# LED42056-Board.net
KiCad netlist of a schematic drawn in EAGLE
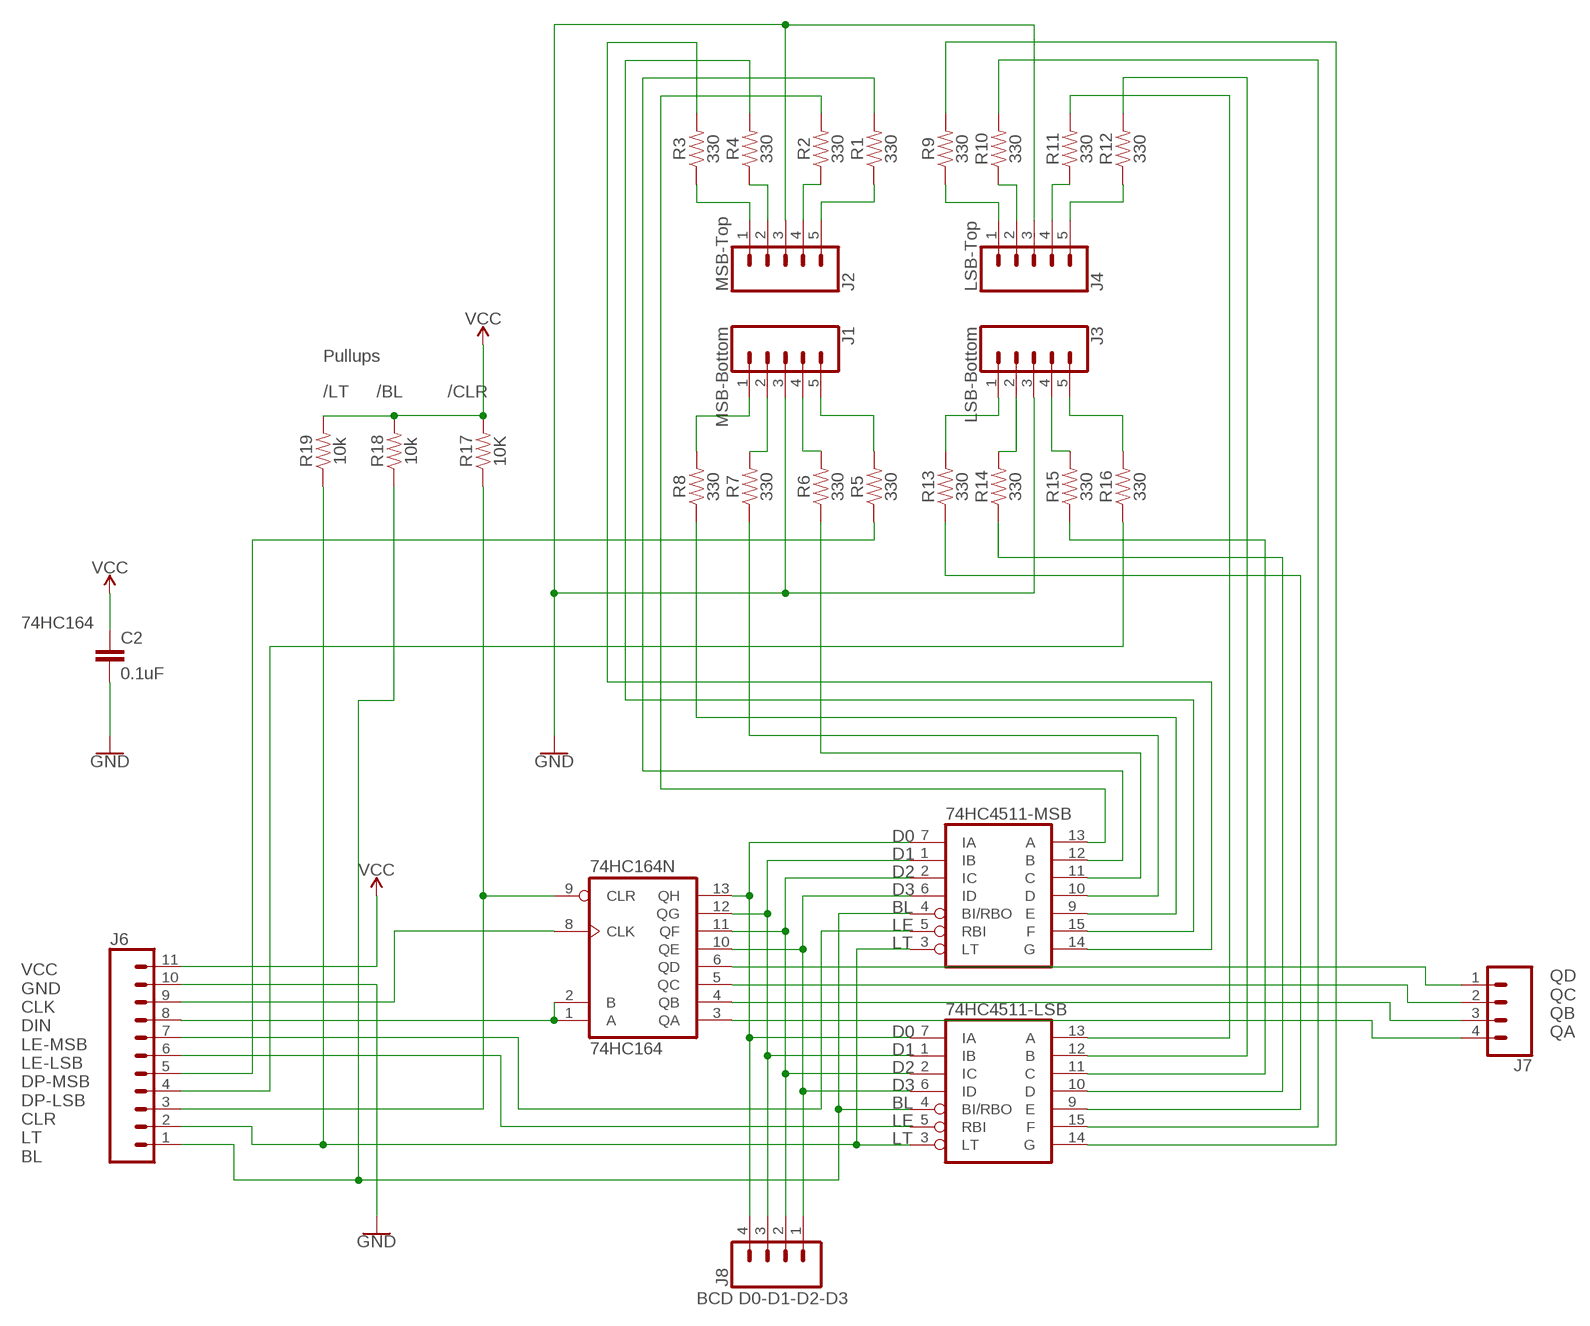
[diagram p0: schematic, sheet 1]

(export (version "E")
  (design (tool "Eeschema 10.0.6"))
  (components
    (comp (ref "74HC164")
      (value "74HC164N")
      (footprint "eagle-import:DIL14")
      (libsource (lib "eagle-import") (part "74164NHC"))
    )
    (comp (ref "74HC4511-LSB")
      (value "74LS47N")
      (footprint "eagle-import:DIL16")
      (libsource (lib "eagle-import") (part "7447NLS"))
    )
    (comp (ref "74HC4511-MSB")
      (value "74LS47N")
      (footprint "eagle-import:DIL16")
      (libsource (lib "eagle-import") (part "7447NLS"))
    )
    (comp (ref "C2")
      (value "0.1uF")
      (footprint "eagle-import:CAP-PTH-2.54")
      (libsource (lib "eagle-import") (part "22PF-PTH-2.54MM-200V-5%"))
    )
    (comp (ref "J1")
      (value "MSB-Bottom")
      (footprint "eagle-import:1X05_LOCK")
      (libsource (lib "eagle-import") (part "CONN_05LOCK"))
    )
    (comp (ref "J2")
      (value "MSB-Top")
      (footprint "eagle-import:1X05_LOCK")
      (libsource (lib "eagle-import") (part "CONN_05LOCK"))
    )
    (comp (ref "J3")
      (value "LSB-Bottom")
      (footprint "eagle-import:1X05_LOCK")
      (libsource (lib "eagle-import") (part "CONN_05LOCK"))
    )
    (comp (ref "J4")
      (value "LSB-Top")
      (footprint "eagle-import:1X05_LOCK")
      (libsource (lib "eagle-import") (part "CONN_05LOCK"))
    )
    (comp (ref "J6")
      (value "CONN_11LOCK")
      (footprint "eagle-import:1X11_LOCK")
      (libsource (lib "eagle-import") (part "CONN_11LOCK"))
    )
    (comp (ref "J7")
      (value "CONN_04LOCK")
      (footprint "eagle-import:1X04_LOCK")
      (libsource (lib "eagle-import") (part "CONN_04LOCK"))
    )
    (comp (ref "J8")
      (value "CONN_04LOCK")
      (footprint "eagle-import:1X04_LOCK")
      (libsource (lib "eagle-import") (part "CONN_04LOCK"))
    )
    (comp (ref "R1")
      (value "330")
      (footprint "eagle-import:AXIAL-0.3")
      (libsource (lib "eagle-import") (part "330OHM-HORIZ-1/10W-5%"))
    )
    (comp (ref "R2")
      (value "330")
      (footprint "eagle-import:AXIAL-0.3")
      (libsource (lib "eagle-import") (part "330OHM-HORIZ-1/10W-5%"))
    )
    (comp (ref "R3")
      (value "330")
      (footprint "eagle-import:AXIAL-0.3")
      (libsource (lib "eagle-import") (part "330OHM-HORIZ-1/10W-5%"))
    )
    (comp (ref "R4")
      (value "330")
      (footprint "eagle-import:AXIAL-0.3")
      (libsource (lib "eagle-import") (part "330OHM-HORIZ-1/10W-5%"))
    )
    (comp (ref "R5")
      (value "330")
      (footprint "eagle-import:AXIAL-0.3")
      (libsource (lib "eagle-import") (part "330OHM-HORIZ-1/10W-5%"))
    )
    (comp (ref "R6")
      (value "330")
      (footprint "eagle-import:AXIAL-0.3")
      (libsource (lib "eagle-import") (part "330OHM-HORIZ-1/10W-5%"))
    )
    (comp (ref "R7")
      (value "330")
      (footprint "eagle-import:AXIAL-0.3")
      (libsource (lib "eagle-import") (part "330OHM-HORIZ-1/10W-5%"))
    )
    (comp (ref "R8")
      (value "330")
      (footprint "eagle-import:AXIAL-0.3")
      (libsource (lib "eagle-import") (part "330OHM-HORIZ-1/10W-5%"))
    )
    (comp (ref "R9")
      (value "330")
      (footprint "eagle-import:AXIAL-0.3")
      (libsource (lib "eagle-import") (part "330OHM-HORIZ-1/10W-5%"))
    )
    (comp (ref "R10")
      (value "330")
      (footprint "eagle-import:AXIAL-0.3")
      (libsource (lib "eagle-import") (part "330OHM-HORIZ-1/10W-5%"))
    )
    (comp (ref "R11")
      (value "330")
      (footprint "eagle-import:AXIAL-0.3")
      (libsource (lib "eagle-import") (part "330OHM-HORIZ-1/10W-5%"))
    )
    (comp (ref "R12")
      (value "330")
      (footprint "eagle-import:AXIAL-0.3")
      (libsource (lib "eagle-import") (part "330OHM-HORIZ-1/10W-5%"))
    )
    (comp (ref "R13")
      (value "330")
      (footprint "eagle-import:AXIAL-0.3")
      (libsource (lib "eagle-import") (part "330OHM-HORIZ-1/10W-5%"))
    )
    (comp (ref "R14")
      (value "330")
      (footprint "eagle-import:AXIAL-0.3")
      (libsource (lib "eagle-import") (part "330OHM-HORIZ-1/10W-5%"))
    )
    (comp (ref "R15")
      (value "330")
      (footprint "eagle-import:AXIAL-0.3")
      (libsource (lib "eagle-import") (part "330OHM-HORIZ-1/10W-5%"))
    )
    (comp (ref "R16")
      (value "330")
      (footprint "eagle-import:AXIAL-0.3")
      (libsource (lib "eagle-import") (part "330OHM-HORIZ-1/10W-5%"))
    )
    (comp (ref "R17")
      (value "10K")
      (footprint "eagle-import:AXIAL-0.3")
      (libsource (lib "eagle-import") (part "330OHM-HORIZ-1/10W-5%"))
    )
    (comp (ref "R18")
      (value "10k")
      (footprint "eagle-import:AXIAL-0.3")
      (libsource (lib "eagle-import") (part "10KOHM-HORIZ-1/4W-1%"))
    )
    (comp (ref "R19")
      (value "10k")
      (footprint "eagle-import:AXIAL-0.3")
      (libsource (lib "eagle-import") (part "10KOHM-HORIZ-1/4W-1%"))
    )
  )
  (nets
    (net (code "1") (name "GND") (class "Default")
      (node (ref "C2") (pin "2") (pinfunction "2_2") (pintype "passive"))
      (node (ref "J1") (pin "3") (pinfunction "3_3") (pintype "passive"))
      (node (ref "J2") (pin "3") (pinfunction "3_3") (pintype "passive"))
      (node (ref "J3") (pin "3") (pinfunction "3_3") (pintype "passive"))
      (node (ref "J4") (pin "3") (pinfunction "3_3") (pintype "passive"))
      (node (ref "J6") (pin "10") (pinfunction "10_10") (pintype "passive"))
    )
    (net (code "2") (name "Net-(74HC164A-A)") (class "Default")
      (node (ref "74HC164") (pin "1") (pinfunction "A_1") (pintype "input"))
      (node (ref "74HC164") (pin "2") (pinfunction "B_2") (pintype "input"))
      (node (ref "J6") (pin "8") (pinfunction "8_8") (pintype "passive"))
    )
    (net (code "3") (name "Net-(74HC164A-CLK)") (class "Default")
      (node (ref "74HC164") (pin "8") (pinfunction "CLK_8") (pintype "input"))
      (node (ref "J6") (pin "9") (pinfunction "9_9") (pintype "passive"))
    )
    (net (code "4") (name "Net-(74HC164A-CLR)") (class "Default")
      (node (ref "74HC164") (pin "9") (pinfunction "CLR_9") (pintype "input"))
      (node (ref "J6") (pin "3") (pinfunction "3_3") (pintype "passive"))
      (node (ref "R17") (pin "P$1") (pinfunction "1_P$1") (pintype "passive"))
    )
    (net (code "5") (name "Net-(74HC164A-QA)") (class "Default")
      (node (ref "74HC164") (pin "3") (pinfunction "QA_3") (pintype "output"))
      (node (ref "J7") (pin "4") (pinfunction "4_4") (pintype "passive"))
    )
    (net (code "6") (name "Net-(74HC164A-QB)") (class "Default")
      (node (ref "74HC164") (pin "4") (pinfunction "QB_4") (pintype "output"))
      (node (ref "J7") (pin "3") (pinfunction "3_3") (pintype "passive"))
    )
    (net (code "7") (name "Net-(74HC164A-QC)") (class "Default")
      (node (ref "74HC164") (pin "5") (pinfunction "QC_5") (pintype "output"))
      (node (ref "J7") (pin "2") (pinfunction "2_2") (pintype "passive"))
    )
    (net (code "8") (name "Net-(74HC164A-QD)") (class "Default")
      (node (ref "74HC164") (pin "6") (pinfunction "QD_6") (pintype "output"))
      (node (ref "J7") (pin "1") (pinfunction "1_1") (pintype "passive"))
    )
    (net (code "9") (name "Net-(74HC164A-QE)") (class "Default")
      (node (ref "74HC164") (pin "10") (pinfunction "QE_10") (pintype "output"))
      (node (ref "74HC4511-LSB") (pin "6") (pinfunction "ID_6") (pintype "input"))
      (node (ref "74HC4511-MSB") (pin "6") (pinfunction "ID_6") (pintype "input"))
      (node (ref "J8") (pin "1") (pinfunction "1_1") (pintype "passive"))
    )
    (net (code "10") (name "Net-(74HC164A-QF)") (class "Default")
      (node (ref "74HC164") (pin "11") (pinfunction "QF_11") (pintype "output"))
      (node (ref "74HC4511-LSB") (pin "2") (pinfunction "IC_2") (pintype "input"))
      (node (ref "74HC4511-MSB") (pin "2") (pinfunction "IC_2") (pintype "input"))
      (node (ref "J8") (pin "2") (pinfunction "2_2") (pintype "passive"))
    )
    (net (code "11") (name "Net-(74HC164A-QG)") (class "Default")
      (node (ref "74HC164") (pin "12") (pinfunction "QG_12") (pintype "output"))
      (node (ref "74HC4511-LSB") (pin "1") (pinfunction "IB_1") (pintype "input"))
      (node (ref "74HC4511-MSB") (pin "1") (pinfunction "IB_1") (pintype "input"))
      (node (ref "J8") (pin "3") (pinfunction "3_3") (pintype "passive"))
    )
    (net (code "12") (name "Net-(74HC164A-QH)") (class "Default")
      (node (ref "74HC164") (pin "13") (pinfunction "QH_13") (pintype "output"))
      (node (ref "74HC4511-LSB") (pin "7") (pinfunction "IA_7") (pintype "input"))
      (node (ref "74HC4511-MSB") (pin "7") (pinfunction "IA_7") (pintype "input"))
      (node (ref "J8") (pin "4") (pinfunction "4_4") (pintype "passive"))
    )
    (net (code "13") (name "Net-(74HC4511-LSBA-A)") (class "Default")
      (node (ref "74HC4511-LSB") (pin "13") (pinfunction "A_13") (pintype "output"))
      (node (ref "R11") (pin "P$2") (pinfunction "2_P$2") (pintype "passive"))
    )
    (net (code "14") (name "Net-(74HC4511-LSBA-B)") (class "Default")
      (node (ref "74HC4511-LSB") (pin "12") (pinfunction "B_12") (pintype "output"))
      (node (ref "R12") (pin "P$2") (pinfunction "2_P$2") (pintype "passive"))
    )
    (net (code "15") (name "Net-(74HC4511-LSBA-BI{slash}RBO)") (class "Default")
      (node (ref "74HC4511-LSB") (pin "4") (pinfunction "BI/RBO_4") (pintype "input"))
      (node (ref "74HC4511-MSB") (pin "4") (pinfunction "BI/RBO_4") (pintype "input"))
      (node (ref "J6") (pin "1") (pinfunction "1_1") (pintype "passive"))
      (node (ref "R18") (pin "P$1") (pinfunction "1_P$1") (pintype "passive"))
    )
    (net (code "16") (name "Net-(74HC4511-LSBA-C)") (class "Default")
      (node (ref "74HC4511-LSB") (pin "11") (pinfunction "C_11") (pintype "output"))
      (node (ref "R15") (pin "P$1") (pinfunction "1_P$1") (pintype "passive"))
    )
    (net (code "17") (name "Net-(74HC4511-LSBA-D)") (class "Default")
      (node (ref "74HC4511-LSB") (pin "10") (pinfunction "D_10") (pintype "output"))
      (node (ref "R14") (pin "P$1") (pinfunction "1_P$1") (pintype "passive"))
    )
    (net (code "18") (name "Net-(74HC4511-LSBA-E)") (class "Default")
      (node (ref "74HC4511-LSB") (pin "9") (pinfunction "E_9") (pintype "output"))
      (node (ref "R13") (pin "P$1") (pinfunction "1_P$1") (pintype "passive"))
    )
    (net (code "19") (name "Net-(74HC4511-LSBA-F)") (class "Default")
      (node (ref "74HC4511-LSB") (pin "15") (pinfunction "F_15") (pintype "output"))
      (node (ref "R10") (pin "P$2") (pinfunction "2_P$2") (pintype "passive"))
    )
    (net (code "20") (name "Net-(74HC4511-LSBA-G)") (class "Default")
      (node (ref "74HC4511-LSB") (pin "14") (pinfunction "G_14") (pintype "output"))
      (node (ref "R9") (pin "P$2") (pinfunction "2_P$2") (pintype "passive"))
    )
    (net (code "21") (name "Net-(74HC4511-LSBA-LT)") (class "Default")
      (node (ref "74HC4511-LSB") (pin "3") (pinfunction "LT_3") (pintype "input"))
      (node (ref "74HC4511-MSB") (pin "3") (pinfunction "LT_3") (pintype "input"))
      (node (ref "J6") (pin "2") (pinfunction "2_2") (pintype "passive"))
      (node (ref "R19") (pin "P$1") (pinfunction "1_P$1") (pintype "passive"))
    )
    (net (code "22") (name "Net-(74HC4511-LSBA-RBI)") (class "Default")
      (node (ref "74HC4511-LSB") (pin "5") (pinfunction "RBI_5") (pintype "input"))
      (node (ref "J6") (pin "6") (pinfunction "6_6") (pintype "passive"))
    )
    (net (code "23") (name "Net-(74HC4511-MSBA-A)") (class "Default")
      (node (ref "74HC4511-MSB") (pin "13") (pinfunction "A_13") (pintype "output"))
      (node (ref "R2") (pin "P$2") (pinfunction "2_P$2") (pintype "passive"))
    )
    (net (code "24") (name "Net-(74HC4511-MSBA-B)") (class "Default")
      (node (ref "74HC4511-MSB") (pin "12") (pinfunction "B_12") (pintype "output"))
      (node (ref "R1") (pin "P$2") (pinfunction "2_P$2") (pintype "passive"))
    )
    (net (code "25") (name "Net-(74HC4511-MSBA-C)") (class "Default")
      (node (ref "74HC4511-MSB") (pin "11") (pinfunction "C_11") (pintype "output"))
      (node (ref "R6") (pin "P$1") (pinfunction "1_P$1") (pintype "passive"))
    )
    (net (code "26") (name "Net-(74HC4511-MSBA-D)") (class "Default")
      (node (ref "74HC4511-MSB") (pin "10") (pinfunction "D_10") (pintype "output"))
      (node (ref "R7") (pin "P$1") (pinfunction "1_P$1") (pintype "passive"))
    )
    (net (code "27") (name "Net-(74HC4511-MSBA-E)") (class "Default")
      (node (ref "74HC4511-MSB") (pin "9") (pinfunction "E_9") (pintype "output"))
      (node (ref "R8") (pin "P$1") (pinfunction "1_P$1") (pintype "passive"))
    )
    (net (code "28") (name "Net-(74HC4511-MSBA-F)") (class "Default")
      (node (ref "74HC4511-MSB") (pin "15") (pinfunction "F_15") (pintype "output"))
      (node (ref "R4") (pin "P$2") (pinfunction "2_P$2") (pintype "passive"))
    )
    (net (code "29") (name "Net-(74HC4511-MSBA-G)") (class "Default")
      (node (ref "74HC4511-MSB") (pin "14") (pinfunction "G_14") (pintype "output"))
      (node (ref "R3") (pin "P$2") (pinfunction "2_P$2") (pintype "passive"))
    )
    (net (code "30") (name "Net-(74HC4511-MSBA-RBI)") (class "Default")
      (node (ref "74HC4511-MSB") (pin "5") (pinfunction "RBI_5") (pintype "input"))
      (node (ref "J6") (pin "7") (pinfunction "7_7") (pintype "passive"))
    )
    (net (code "31") (name "Net-(R1-1)") (class "Default")
      (node (ref "J2") (pin "5") (pinfunction "5_5") (pintype "passive"))
      (node (ref "R1") (pin "P$1") (pinfunction "1_P$1") (pintype "passive"))
    )
    (net (code "32") (name "Net-(R2-1)") (class "Default")
      (node (ref "J2") (pin "4") (pinfunction "4_4") (pintype "passive"))
      (node (ref "R2") (pin "P$1") (pinfunction "1_P$1") (pintype "passive"))
    )
    (net (code "33") (name "Net-(R3-1)") (class "Default")
      (node (ref "J2") (pin "1") (pinfunction "1_1") (pintype "passive"))
      (node (ref "R3") (pin "P$1") (pinfunction "1_P$1") (pintype "passive"))
    )
    (net (code "34") (name "Net-(R4-1)") (class "Default")
      (node (ref "J2") (pin "2") (pinfunction "2_2") (pintype "passive"))
      (node (ref "R4") (pin "P$1") (pinfunction "1_P$1") (pintype "passive"))
    )
    (net (code "35") (name "Net-(R5-1)") (class "Default")
      (node (ref "J6") (pin "5") (pinfunction "5_5") (pintype "passive"))
      (node (ref "R5") (pin "P$1") (pinfunction "1_P$1") (pintype "passive"))
    )
    (net (code "36") (name "Net-(R5-2)") (class "Default")
      (node (ref "J1") (pin "5") (pinfunction "5_5") (pintype "passive"))
      (node (ref "R5") (pin "P$2") (pinfunction "2_P$2") (pintype "passive"))
    )
    (net (code "37") (name "Net-(R6-2)") (class "Default")
      (node (ref "J1") (pin "4") (pinfunction "4_4") (pintype "passive"))
      (node (ref "R6") (pin "P$2") (pinfunction "2_P$2") (pintype "passive"))
    )
    (net (code "38") (name "Net-(R7-2)") (class "Default")
      (node (ref "J1") (pin "2") (pinfunction "2_2") (pintype "passive"))
      (node (ref "R7") (pin "P$2") (pinfunction "2_P$2") (pintype "passive"))
    )
    (net (code "39") (name "Net-(R8-2)") (class "Default")
      (node (ref "J1") (pin "1") (pinfunction "1_1") (pintype "passive"))
      (node (ref "R8") (pin "P$2") (pinfunction "2_P$2") (pintype "passive"))
    )
    (net (code "40") (name "Net-(R9-1)") (class "Default")
      (node (ref "J4") (pin "1") (pinfunction "1_1") (pintype "passive"))
      (node (ref "R9") (pin "P$1") (pinfunction "1_P$1") (pintype "passive"))
    )
    (net (code "41") (name "Net-(R10-1)") (class "Default")
      (node (ref "J4") (pin "2") (pinfunction "2_2") (pintype "passive"))
      (node (ref "R10") (pin "P$1") (pinfunction "1_P$1") (pintype "passive"))
    )
    (net (code "42") (name "Net-(R11-1)") (class "Default")
      (node (ref "J4") (pin "4") (pinfunction "4_4") (pintype "passive"))
      (node (ref "R11") (pin "P$1") (pinfunction "1_P$1") (pintype "passive"))
    )
    (net (code "43") (name "Net-(R12-1)") (class "Default")
      (node (ref "J4") (pin "5") (pinfunction "5_5") (pintype "passive"))
      (node (ref "R12") (pin "P$1") (pinfunction "1_P$1") (pintype "passive"))
    )
    (net (code "44") (name "Net-(R13-2)") (class "Default")
      (node (ref "J3") (pin "1") (pinfunction "1_1") (pintype "passive"))
      (node (ref "R13") (pin "P$2") (pinfunction "2_P$2") (pintype "passive"))
    )
    (net (code "45") (name "Net-(R14-2)") (class "Default")
      (node (ref "J3") (pin "2") (pinfunction "2_2") (pintype "passive"))
      (node (ref "R14") (pin "P$2") (pinfunction "2_P$2") (pintype "passive"))
    )
    (net (code "46") (name "Net-(R15-2)") (class "Default")
      (node (ref "J3") (pin "4") (pinfunction "4_4") (pintype "passive"))
      (node (ref "R15") (pin "P$2") (pinfunction "2_P$2") (pintype "passive"))
    )
    (net (code "47") (name "Net-(R16-1)") (class "Default")
      (node (ref "J6") (pin "4") (pinfunction "4_4") (pintype "passive"))
      (node (ref "R16") (pin "P$1") (pinfunction "1_P$1") (pintype "passive"))
    )
    (net (code "48") (name "Net-(R16-2)") (class "Default")
      (node (ref "J3") (pin "5") (pinfunction "5_5") (pintype "passive"))
      (node (ref "R16") (pin "P$2") (pinfunction "2_P$2") (pintype "passive"))
    )
    (net (code "49") (name "VCC") (class "Default")
      (node (ref "C2") (pin "1") (pinfunction "1_1") (pintype "passive"))
      (node (ref "J6") (pin "11") (pinfunction "11_11") (pintype "passive"))
      (node (ref "R17") (pin "P$2") (pinfunction "2_P$2") (pintype "passive"))
      (node (ref "R18") (pin "P$2") (pinfunction "2_P$2") (pintype "passive"))
      (node (ref "R19") (pin "P$2") (pinfunction "2_P$2") (pintype "passive"))
    )
  )
)
